# EN-C200_RA0_MCU.net
KiCad netlist of a schematic drawn in Altium Designer
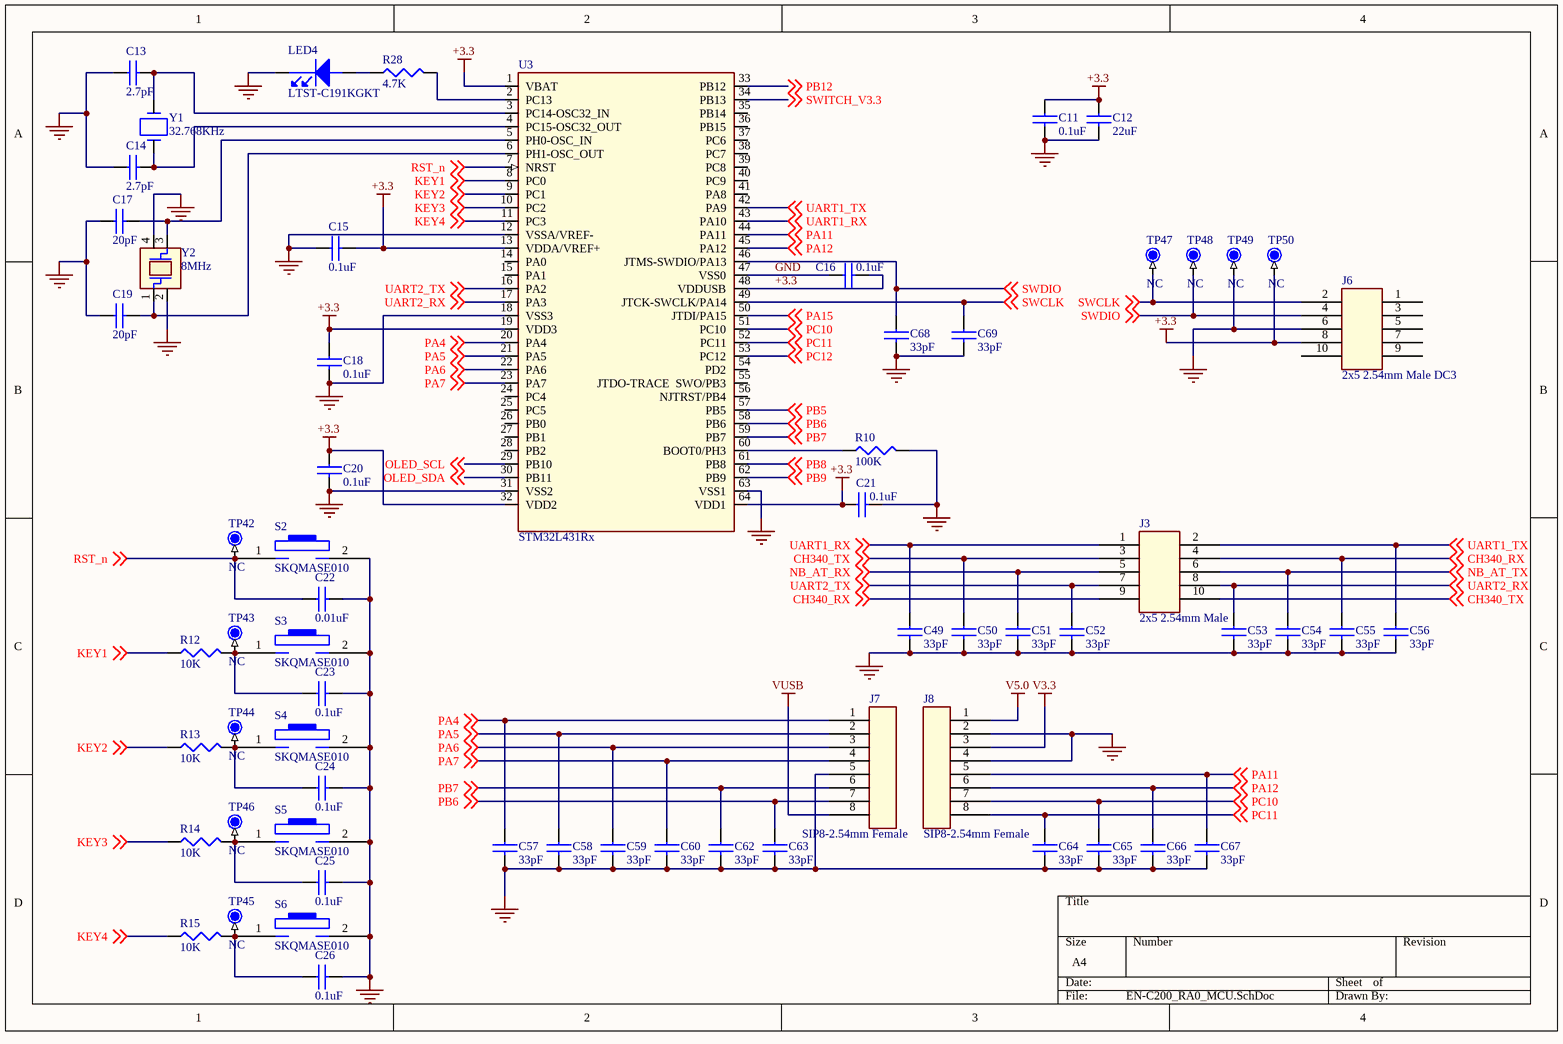
[diagram p0: EN-C200_RA0_MCU.SchDoc]

(export (version "E")
  (design (tool "Eeschema 10.0.6"))
  (components
    (comp (ref "C11") (value "0.1uF") (footprint "SC0603") (libsource (lib "EN-C200_RA0") (part "CAP NP")))
    (comp (ref "C12") (value "22uF") (footprint "SC0805") (libsource (lib "EN-C200_RA0") (part "CAP NP")))
    (comp (ref "C13") (value "2.7pF") (footprint "SC0603") (libsource (lib "EN-C200_RA0") (part "CAP NP")))
    (comp (ref "C14") (value "2.7pF") (footprint "SC0603") (libsource (lib "EN-C200_RA0") (part "CAP NP")))
    (comp (ref "C15") (value "0.1uF") (footprint "SC0603") (libsource (lib "EN-C200_RA0") (part "CAP NP")))
    (comp (ref "C16") (value "0.1uF") (footprint "SC0603") (libsource (lib "EN-C200_RA0") (part "CAP NP")))
    (comp (ref "C17") (value "20pF") (footprint "SC0603") (libsource (lib "EN-C200_RA0") (part "CAP NP")))
    (comp (ref "C18") (value "0.1uF") (footprint "SC0603") (libsource (lib "EN-C200_RA0") (part "CAP NP")))
    (comp (ref "C19") (value "20pF") (footprint "SC0603") (libsource (lib "EN-C200_RA0") (part "CAP NP")))
    (comp (ref "C20") (value "0.1uF") (footprint "SC0603") (libsource (lib "EN-C200_RA0") (part "CAP NP")))
    (comp (ref "C21") (value "0.1uF") (footprint "SC0603") (libsource (lib "EN-C200_RA0") (part "CAP NP")))
    (comp (ref "C22") (value "0.01uF") (footprint "SC0603") (libsource (lib "EN-C200_RA0") (part "CAP NP")))
    (comp (ref "C23") (value "0.1uF") (footprint "SC0603") (libsource (lib "EN-C200_RA0") (part "CAP NP")))
    (comp (ref "C24") (value "0.1uF") (footprint "SC0603") (libsource (lib "EN-C200_RA0") (part "CAP NP")))
    (comp (ref "C25") (value "0.1uF") (footprint "SC0603") (libsource (lib "EN-C200_RA0") (part "CAP NP")))
    (comp (ref "C26") (value "0.1uF") (footprint "SC0603") (libsource (lib "EN-C200_RA0") (part "CAP NP")))
    (comp (ref "C49") (value "33pF") (footprint "SC0603") (libsource (lib "EN-C200_RA0") (part "CAP NP")))
    (comp (ref "C50") (value "33pF") (footprint "SC0603") (libsource (lib "EN-C200_RA0") (part "CAP NP")))
    (comp (ref "C51") (value "33pF") (footprint "SC0603") (libsource (lib "EN-C200_RA0") (part "CAP NP")))
    (comp (ref "C52") (value "33pF") (footprint "SC0603") (libsource (lib "EN-C200_RA0") (part "CAP NP")))
    (comp (ref "C53") (value "33pF") (footprint "SC0603") (libsource (lib "EN-C200_RA0") (part "CAP NP")))
    (comp (ref "C54") (value "33pF") (footprint "SC0603") (libsource (lib "EN-C200_RA0") (part "CAP NP")))
    (comp (ref "C55") (value "33pF") (footprint "SC0603") (libsource (lib "EN-C200_RA0") (part "CAP NP")))
    (comp (ref "C56") (value "33pF") (footprint "SC0603") (libsource (lib "EN-C200_RA0") (part "CAP NP")))
    (comp (ref "C57") (value "33pF") (footprint "SC0603") (libsource (lib "EN-C200_RA0") (part "CAP NP")))
    (comp (ref "C58") (value "33pF") (footprint "SC0603") (libsource (lib "EN-C200_RA0") (part "CAP NP")))
    (comp (ref "C59") (value "33pF") (footprint "SC0603") (libsource (lib "EN-C200_RA0") (part "CAP NP")))
    (comp (ref "C60") (value "33pF") (footprint "SC0603") (libsource (lib "EN-C200_RA0") (part "CAP NP")))
    (comp (ref "C62") (value "33pF") (footprint "SC0603") (libsource (lib "EN-C200_RA0") (part "CAP NP")))
    (comp (ref "C63") (value "33pF") (footprint "SC0603") (libsource (lib "EN-C200_RA0") (part "CAP NP")))
    (comp (ref "C64") (value "33pF") (footprint "SC0603") (libsource (lib "EN-C200_RA0") (part "CAP NP")))
    (comp (ref "C65") (value "33pF") (footprint "SC0603") (libsource (lib "EN-C200_RA0") (part "CAP NP")))
    (comp (ref "C66") (value "33pF") (footprint "SC0603") (libsource (lib "EN-C200_RA0") (part "CAP NP")))
    (comp (ref "C67") (value "33pF") (footprint "SC0603") (libsource (lib "EN-C200_RA0") (part "CAP NP")))
    (comp (ref "C68") (value "33pF") (footprint "SC0603") (libsource (lib "EN-C200_RA0") (part "CAP NP")))
    (comp (ref "C69") (value "33pF") (footprint "SC0603") (libsource (lib "EN-C200_RA0") (part "CAP NP")))
    (comp (ref "J3")
      (value "2x5 2.54mm Male")
      (footprint "SIP-2X5P-100")
      (libsource (lib "") (part "CON10A_1"))
    )
    (comp (ref "J6")
      (value "2x5 2.54mm Male DC3")
      (footprint "SIP-2X5P-100-DS")
      (libsource (lib "EN-C200_RA0") (part "CON10A"))
    )
    (comp (ref "J7")
      (value "SIP8-2.54mm Female")
      (footprint "SIP-8P-100")
      (libsource (lib "EN-C200_RA0") (part "HEADER8"))
    )
    (comp (ref "J8")
      (value "SIP8-2.54mm Female")
      (footprint "SIP-8P-100")
      (libsource (lib "") (part "HEADER8_1"))
    )
    (comp (ref "LED4")
      (value "LTST-C191KGKT")
      (footprint "HSD0603-LED")
      (libsource (lib "EN-C200_RA0") (part "LED"))
    )
    (comp (ref "R10") (value "100K") (footprint "SR0603") (libsource (lib "EN-C200_RA0") (part "RESISTOR")))
    (comp (ref "R12") (value "10K") (footprint "SR0603") (libsource (lib "EN-C200_RA0") (part "RESISTOR")))
    (comp (ref "R13") (value "10K") (footprint "SR0603") (libsource (lib "EN-C200_RA0") (part "RESISTOR")))
    (comp (ref "R14") (value "10K") (footprint "SR0603") (libsource (lib "EN-C200_RA0") (part "RESISTOR")))
    (comp (ref "R15") (value "10K") (footprint "SR0603") (libsource (lib "EN-C200_RA0") (part "RESISTOR")))
    (comp (ref "R28") (value "4.7K") (footprint "SR0603") (libsource (lib "EN-C200_RA0") (part "RESISTOR")))
    (comp (ref "S2")
      (value "SKQMASE010")
      (footprint "SW2-240X140")
      (libsource (lib "EN-C200_RA0") (part "PUSH-KEY"))
    )
    (comp (ref "S3")
      (value "SKQMASE010")
      (footprint "SW2-240X140")
      (libsource (lib "EN-C200_RA0") (part "PUSH-KEY"))
    )
    (comp (ref "S4")
      (value "SKQMASE010")
      (footprint "SW2-240X140")
      (libsource (lib "EN-C200_RA0") (part "PUSH-KEY"))
    )
    (comp (ref "S5")
      (value "SKQMASE010")
      (footprint "SW2-240X140")
      (libsource (lib "EN-C200_RA0") (part "PUSH-KEY"))
    )
    (comp (ref "S6")
      (value "SKQMASE010")
      (footprint "SW2-240X140")
      (libsource (lib "EN-C200_RA0") (part "PUSH-KEY"))
    )
    (comp (ref "TP42") (value "NC") (footprint "TP32-SMD") (libsource (lib "EN-C200_RA0") (part "TP")))
    (comp (ref "TP43") (value "NC") (footprint "TP32-SMD") (libsource (lib "EN-C200_RA0") (part "TP")))
    (comp (ref "TP44") (value "NC") (footprint "TP32-SMD") (libsource (lib "EN-C200_RA0") (part "TP")))
    (comp (ref "TP45") (value "NC") (footprint "TP32-SMD") (libsource (lib "EN-C200_RA0") (part "TP")))
    (comp (ref "TP46") (value "NC") (footprint "TP32-SMD") (libsource (lib "EN-C200_RA0") (part "TP")))
    (comp (ref "TP47") (value "NC") (footprint "TP32-SMD") (libsource (lib "EN-C200_RA0") (part "TP")))
    (comp (ref "TP48") (value "NC") (footprint "TP32-SMD") (libsource (lib "EN-C200_RA0") (part "TP")))
    (comp (ref "TP49") (value "NC") (footprint "TP32-SMD") (libsource (lib "EN-C200_RA0") (part "TP")))
    (comp (ref "TP50") (value "NC") (footprint "TP32-SMD") (libsource (lib "EN-C200_RA0") (part "TP")))
    (comp (ref "U3")
      (value "STM32L431Rx")
      (footprint "QFP64D-050-1010L")
      (libsource (lib "EN-C200_RA0") (part "STM32L431Rx"))
    )
    (comp (ref "Y1")
      (value "32.768KHz")
      (footprint "FC-135_110")
      (libsource (lib "EN-C200_RA0") (part "CRYSTAL2P"))
    )
    (comp (ref "Y2")
      (value "8MHz")
      (footprint "HSX4-0503B")
      (libsource (lib "EN-C200_RA0") (part "CRYSTAL4P"))
    )
  )
  (nets
    (net (code "1") (name "+3.3") (class "Default")
      (node (ref "C11") (pin "1") (pinfunction "1_1") (pintype "passive"))
      (node (ref "C12") (pin "1") (pinfunction "1_1") (pintype "passive"))
      (node (ref "C15") (pin "2") (pinfunction "2_2") (pintype "passive"))
      (node (ref "C16") (pin "2") (pinfunction "2_2") (pintype "passive"))
      (node (ref "C18") (pin "1") (pinfunction "1_1") (pintype "passive"))
      (node (ref "C20") (pin "1") (pinfunction "1_1") (pintype "passive"))
      (node (ref "C21") (pin "1") (pinfunction "1_1") (pintype "passive"))
      (node (ref "J6") (pin "8") (pinfunction "8_8") (pintype "passive"))
      (node (ref "TP50") (pin "1") (pinfunction "1_1") (pintype "input"))
      (node (ref "U3") (pin "1") (pinfunction "VBAT_1") (pintype "power_in"))
      (node (ref "U3") (pin "13") (pinfunction "VDDA/VREF+_13") (pintype "power_in"))
      (node (ref "U3") (pin "19") (pinfunction "VDD3_19") (pintype "power_in"))
      (node (ref "U3") (pin "32") (pinfunction "VDD2_32") (pintype "power_in"))
      (node (ref "U3") (pin "48") (pinfunction "VDDUSB_48") (pintype "power_in"))
      (node (ref "U3") (pin "64") (pinfunction "VDD1_64") (pintype "power_in"))
    )
    (net (code "2") (name "CH340_RX") (class "Default")
      (node (ref "C55") (pin "1") (pinfunction "1_1") (pintype "passive"))
      (node (ref "J3") (pin "4") (pinfunction "4_4") (pintype "passive"))
      (node (ref "J3") (pin "9") (pinfunction "9_9") (pintype "passive"))
    )
    (net (code "3") (name "CH340_TX") (class "Default")
      (node (ref "C50") (pin "1") (pinfunction "1_1") (pintype "passive"))
      (node (ref "J3") (pin "10") (pinfunction "10_10") (pintype "passive"))
      (node (ref "J3") (pin "3") (pinfunction "3_3") (pintype "passive"))
    )
    (net (code "4") (name "GND") (class "Default")
      (node (ref "C11") (pin "2") (pinfunction "2_2") (pintype "passive"))
      (node (ref "C12") (pin "2") (pinfunction "2_2") (pintype "passive"))
      (node (ref "C13") (pin "1") (pinfunction "1_1") (pintype "passive"))
      (node (ref "C14") (pin "1") (pinfunction "1_1") (pintype "passive"))
      (node (ref "C15") (pin "1") (pinfunction "1_1") (pintype "passive"))
      (node (ref "C16") (pin "1") (pinfunction "1_1") (pintype "passive"))
      (node (ref "C17") (pin "1") (pinfunction "1_1") (pintype "passive"))
      (node (ref "C18") (pin "2") (pinfunction "2_2") (pintype "passive"))
      (node (ref "C19") (pin "1") (pinfunction "1_1") (pintype "passive"))
      (node (ref "C20") (pin "2") (pinfunction "2_2") (pintype "passive"))
      (node (ref "C21") (pin "2") (pinfunction "2_2") (pintype "passive"))
      (node (ref "C22") (pin "2") (pinfunction "2_2") (pintype "passive"))
      (node (ref "C23") (pin "2") (pinfunction "2_2") (pintype "passive"))
      (node (ref "C24") (pin "2") (pinfunction "2_2") (pintype "passive"))
      (node (ref "C25") (pin "2") (pinfunction "2_2") (pintype "passive"))
      (node (ref "C26") (pin "2") (pinfunction "2_2") (pintype "passive"))
      (node (ref "C49") (pin "2") (pinfunction "2_2") (pintype "passive"))
      (node (ref "C50") (pin "2") (pinfunction "2_2") (pintype "passive"))
      (node (ref "C51") (pin "2") (pinfunction "2_2") (pintype "passive"))
      (node (ref "C52") (pin "2") (pinfunction "2_2") (pintype "passive"))
      (node (ref "C53") (pin "2") (pinfunction "2_2") (pintype "passive"))
      (node (ref "C54") (pin "2") (pinfunction "2_2") (pintype "passive"))
      (node (ref "C55") (pin "2") (pinfunction "2_2") (pintype "passive"))
      (node (ref "C56") (pin "2") (pinfunction "2_2") (pintype "passive"))
      (node (ref "C57") (pin "2") (pinfunction "2_2") (pintype "passive"))
      (node (ref "C58") (pin "2") (pinfunction "2_2") (pintype "passive"))
      (node (ref "C59") (pin "2") (pinfunction "2_2") (pintype "passive"))
      (node (ref "C60") (pin "2") (pinfunction "2_2") (pintype "passive"))
      (node (ref "C62") (pin "2") (pinfunction "2_2") (pintype "passive"))
      (node (ref "C63") (pin "2") (pinfunction "2_2") (pintype "passive"))
      (node (ref "C64") (pin "2") (pinfunction "2_2") (pintype "passive"))
      (node (ref "C65") (pin "2") (pinfunction "2_2") (pintype "passive"))
      (node (ref "C66") (pin "2") (pinfunction "2_2") (pintype "passive"))
      (node (ref "C67") (pin "2") (pinfunction "2_2") (pintype "passive"))
      (node (ref "C68") (pin "2") (pinfunction "2_2") (pintype "passive"))
      (node (ref "C69") (pin "2") (pinfunction "2_2") (pintype "passive"))
      (node (ref "J6") (pin "6") (pinfunction "6_6") (pintype "passive"))
      (node (ref "J7") (pin "5") (pinfunction "5_5") (pintype "passive"))
      (node (ref "J8") (pin "2") (pinfunction "2_2") (pintype "passive"))
      (node (ref "J8") (pin "4") (pinfunction "4_4") (pintype "passive"))
      (node (ref "LED4") (pin "2") (pinfunction "2_2") (pintype "passive"))
      (node (ref "R10") (pin "2") (pinfunction "2_2") (pintype "passive"))
      (node (ref "S2") (pin "2") (pinfunction "B_2") (pintype "passive"))
      (node (ref "S3") (pin "2") (pinfunction "B_2") (pintype "passive"))
      (node (ref "S4") (pin "2") (pinfunction "B_2") (pintype "passive"))
      (node (ref "S5") (pin "2") (pinfunction "B_2") (pintype "passive"))
      (node (ref "S6") (pin "2") (pinfunction "B_2") (pintype "passive"))
      (node (ref "TP49") (pin "1") (pinfunction "1_1") (pintype "input"))
      (node (ref "U3") (pin "12") (pinfunction "VSSA/VREF-_12") (pintype "power_in"))
      (node (ref "U3") (pin "18") (pinfunction "VSS3_18") (pintype "power_in"))
      (node (ref "U3") (pin "31") (pinfunction "VSS2_31") (pintype "power_in"))
      (node (ref "U3") (pin "47") (pinfunction "VSS0_47") (pintype "power_in"))
      (node (ref "U3") (pin "63") (pinfunction "VSS1_63") (pintype "power_in"))
      (node (ref "Y2") (pin "2") (pinfunction "2_2") (pintype "passive"))
      (node (ref "Y2") (pin "4") (pinfunction "4_4") (pintype "passive"))
    )
    (net (code "5") (name "KEY1") (class "Default")
      (node (ref "R12") (pin "1") (pinfunction "1_1") (pintype "passive"))
      (node (ref "U3") (pin "8") (pinfunction "PC0_8") (pintype "bidirectional"))
    )
    (net (code "6") (name "KEY2") (class "Default")
      (node (ref "R13") (pin "1") (pinfunction "1_1") (pintype "passive"))
      (node (ref "U3") (pin "9") (pinfunction "PC1_9") (pintype "bidirectional"))
    )
    (net (code "7") (name "KEY3") (class "Default")
      (node (ref "R14") (pin "1") (pinfunction "1_1") (pintype "passive"))
      (node (ref "U3") (pin "10") (pinfunction "PC2_10") (pintype "bidirectional"))
    )
    (net (code "8") (name "KEY4") (class "Default")
      (node (ref "R15") (pin "1") (pinfunction "1_1") (pintype "passive"))
      (node (ref "U3") (pin "11") (pinfunction "PC3_11") (pintype "bidirectional"))
    )
    (net (code "9") (name "NB_AT_RX") (class "Default")
      (node (ref "C51") (pin "1") (pinfunction "1_1") (pintype "passive"))
      (node (ref "J3") (pin "5") (pinfunction "5_5") (pintype "passive"))
    )
    (net (code "10") (name "NB_AT_TX") (class "Default")
      (node (ref "C54") (pin "1") (pinfunction "1_1") (pintype "passive"))
      (node (ref "J3") (pin "6") (pinfunction "6_6") (pintype "passive"))
    )
    (net (code "11") (name "Net-(LED4-Pad1)") (class "Default")
      (node (ref "LED4") (pin "1") (pinfunction "1_1") (pintype "passive"))
      (node (ref "R28") (pin "1") (pinfunction "1_1") (pintype "passive"))
    )
    (net (code "12") (name "Net-(S3-A)") (class "Default")
      (node (ref "C23") (pin "1") (pinfunction "1_1") (pintype "passive"))
      (node (ref "R12") (pin "2") (pinfunction "2_2") (pintype "passive"))
      (node (ref "S3") (pin "1") (pinfunction "A_1") (pintype "passive"))
      (node (ref "TP43") (pin "1") (pinfunction "1_1") (pintype "input"))
    )
    (net (code "13") (name "Net-(S4-A)") (class "Default")
      (node (ref "C24") (pin "1") (pinfunction "1_1") (pintype "passive"))
      (node (ref "R13") (pin "2") (pinfunction "2_2") (pintype "passive"))
      (node (ref "S4") (pin "1") (pinfunction "A_1") (pintype "passive"))
      (node (ref "TP44") (pin "1") (pinfunction "1_1") (pintype "input"))
    )
    (net (code "14") (name "Net-(S5-A)") (class "Default")
      (node (ref "C25") (pin "1") (pinfunction "1_1") (pintype "passive"))
      (node (ref "R14") (pin "2") (pinfunction "2_2") (pintype "passive"))
      (node (ref "S5") (pin "1") (pinfunction "A_1") (pintype "passive"))
      (node (ref "TP46") (pin "1") (pinfunction "1_1") (pintype "input"))
    )
    (net (code "15") (name "Net-(S6-A)") (class "Default")
      (node (ref "C26") (pin "1") (pinfunction "1_1") (pintype "passive"))
      (node (ref "R15") (pin "2") (pinfunction "2_2") (pintype "passive"))
      (node (ref "S6") (pin "1") (pinfunction "A_1") (pintype "passive"))
      (node (ref "TP45") (pin "1") (pinfunction "1_1") (pintype "input"))
    )
    (net (code "16") (name "Net-(U3-BOOT0{slash}PH3)") (class "Default")
      (node (ref "R10") (pin "1") (pinfunction "1_1") (pintype "passive"))
      (node (ref "U3") (pin "60") (pinfunction "BOOT0/PH3_60") (pintype "bidirectional"))
    )
    (net (code "17") (name "Net-(U3-PC13)") (class "Default")
      (node (ref "R28") (pin "2") (pinfunction "2_2") (pintype "passive"))
      (node (ref "U3") (pin "2") (pinfunction "PC13_2") (pintype "bidirectional"))
    )
    (net (code "18") (name "Net-(U3-PC14-OSC32_IN)") (class "Default")
      (node (ref "C13") (pin "2") (pinfunction "2_2") (pintype "passive"))
      (node (ref "U3") (pin "3") (pinfunction "PC14-OSC32_IN_3") (pintype "bidirectional"))
      (node (ref "Y1") (pin "2") (pinfunction "2_2") (pintype "passive"))
    )
    (net (code "19") (name "Net-(U3-PC15-OSC32_OUT)") (class "Default")
      (node (ref "C14") (pin "2") (pinfunction "2_2") (pintype "passive"))
      (node (ref "U3") (pin "4") (pinfunction "PC15-OSC32_OUT_4") (pintype "bidirectional"))
      (node (ref "Y1") (pin "1") (pinfunction "1_1") (pintype "passive"))
    )
    (net (code "20") (name "Net-(U3-PH0-OSC_IN)") (class "Default")
      (node (ref "C17") (pin "2") (pinfunction "2_2") (pintype "passive"))
      (node (ref "U3") (pin "5") (pinfunction "PH0-OSC_IN_5") (pintype "bidirectional"))
      (node (ref "Y2") (pin "3") (pinfunction "COUT_3") (pintype "passive"))
    )
    (net (code "21") (name "Net-(U3-PH1-OSC_OUT)") (class "Default")
      (node (ref "C19") (pin "2") (pinfunction "2_2") (pintype "passive"))
      (node (ref "U3") (pin "6") (pinfunction "PH1-OSC_OUT_6") (pintype "bidirectional"))
      (node (ref "Y2") (pin "1") (pinfunction "CIN_1") (pintype "passive"))
    )
    (net (code "22") (name "OLED_SCL") (class "Default")
      (node (ref "U3") (pin "29") (pinfunction "PB10_29") (pintype "bidirectional"))
    )
    (net (code "23") (name "OLED_SDA") (class "Default")
      (node (ref "U3") (pin "30") (pinfunction "PB11_30") (pintype "bidirectional"))
    )
    (net (code "24") (name "PA4") (class "Default")
      (node (ref "C57") (pin "1") (pinfunction "1_1") (pintype "passive"))
      (node (ref "J7") (pin "1") (pinfunction "1_1") (pintype "passive"))
      (node (ref "U3") (pin "20") (pinfunction "PA4_20") (pintype "bidirectional"))
    )
    (net (code "25") (name "PA5") (class "Default")
      (node (ref "C58") (pin "1") (pinfunction "1_1") (pintype "passive"))
      (node (ref "J7") (pin "2") (pinfunction "2_2") (pintype "passive"))
      (node (ref "U3") (pin "21") (pinfunction "PA5_21") (pintype "bidirectional"))
    )
    (net (code "26") (name "PA6") (class "Default")
      (node (ref "C59") (pin "1") (pinfunction "1_1") (pintype "passive"))
      (node (ref "J7") (pin "3") (pinfunction "3_3") (pintype "passive"))
      (node (ref "U3") (pin "22") (pinfunction "PA6_22") (pintype "bidirectional"))
    )
    (net (code "27") (name "PA7") (class "Default")
      (node (ref "C60") (pin "1") (pinfunction "1_1") (pintype "passive"))
      (node (ref "J7") (pin "4") (pinfunction "4_4") (pintype "passive"))
      (node (ref "U3") (pin "23") (pinfunction "PA7_23") (pintype "bidirectional"))
    )
    (net (code "28") (name "PA11") (class "Default")
      (node (ref "C67") (pin "1") (pinfunction "1_1") (pintype "passive"))
      (node (ref "J8") (pin "5") (pinfunction "5_5") (pintype "passive"))
      (node (ref "U3") (pin "44") (pinfunction "PA11_44") (pintype "bidirectional"))
    )
    (net (code "29") (name "PA12") (class "Default")
      (node (ref "C66") (pin "1") (pinfunction "1_1") (pintype "passive"))
      (node (ref "J8") (pin "6") (pinfunction "6_6") (pintype "passive"))
      (node (ref "U3") (pin "45") (pinfunction "PA12_45") (pintype "bidirectional"))
    )
    (net (code "30") (name "PA15") (class "Default")
      (node (ref "U3") (pin "50") (pinfunction "JTDI/PA15_50") (pintype "bidirectional"))
    )
    (net (code "31") (name "PB5") (class "Default")
      (node (ref "U3") (pin "57") (pinfunction "PB5_57") (pintype "bidirectional"))
    )
    (net (code "32") (name "PB6") (class "Default")
      (node (ref "C63") (pin "1") (pinfunction "1_1") (pintype "passive"))
      (node (ref "J7") (pin "7") (pinfunction "7_7") (pintype "passive"))
      (node (ref "U3") (pin "58") (pinfunction "PB6_58") (pintype "bidirectional"))
    )
    (net (code "33") (name "PB7") (class "Default")
      (node (ref "C62") (pin "1") (pinfunction "1_1") (pintype "passive"))
      (node (ref "J7") (pin "6") (pinfunction "6_6") (pintype "passive"))
      (node (ref "U3") (pin "59") (pinfunction "PB7_59") (pintype "bidirectional"))
    )
    (net (code "34") (name "PB8") (class "Default")
      (node (ref "U3") (pin "61") (pinfunction "PB8_61") (pintype "bidirectional"))
    )
    (net (code "35") (name "PB9") (class "Default")
      (node (ref "U3") (pin "62") (pinfunction "PB9_62") (pintype "bidirectional"))
    )
    (net (code "36") (name "PB12") (class "Default")
      (node (ref "U3") (pin "33") (pinfunction "PB12_33") (pintype "bidirectional"))
    )
    (net (code "37") (name "PC10") (class "Default")
      (node (ref "C65") (pin "1") (pinfunction "1_1") (pintype "passive"))
      (node (ref "J8") (pin "7") (pinfunction "7_7") (pintype "passive"))
      (node (ref "U3") (pin "51") (pinfunction "PC10_51") (pintype "bidirectional"))
    )
    (net (code "38") (name "PC11") (class "Default")
      (node (ref "C64") (pin "1") (pinfunction "1_1") (pintype "passive"))
      (node (ref "J8") (pin "8") (pinfunction "8_8") (pintype "passive"))
      (node (ref "U3") (pin "52") (pinfunction "PC11_52") (pintype "bidirectional"))
    )
    (net (code "39") (name "PC12") (class "Default")
      (node (ref "U3") (pin "53") (pinfunction "PC12_53") (pintype "bidirectional"))
    )
    (net (code "40") (name "RST_n") (class "Default")
      (node (ref "C22") (pin "1") (pinfunction "1_1") (pintype "passive"))
      (node (ref "S2") (pin "1") (pinfunction "A_1") (pintype "passive"))
      (node (ref "TP42") (pin "1") (pinfunction "1_1") (pintype "input"))
      (node (ref "U3") (pin "7") (pinfunction "NRST_7") (pintype "input"))
    )
    (net (code "41") (name "SWCLK") (class "Default")
      (node (ref "C69") (pin "1") (pinfunction "1_1") (pintype "passive"))
      (node (ref "J6") (pin "2") (pinfunction "2_2") (pintype "passive"))
      (node (ref "TP47") (pin "1") (pinfunction "1_1") (pintype "input"))
      (node (ref "U3") (pin "49") (pinfunction "JTCK-SWCLK/PA14_49") (pintype "bidirectional"))
    )
    (net (code "42") (name "SWDIO") (class "Default")
      (node (ref "C68") (pin "1") (pinfunction "1_1") (pintype "passive"))
      (node (ref "J6") (pin "4") (pinfunction "4_4") (pintype "passive"))
      (node (ref "TP48") (pin "1") (pinfunction "1_1") (pintype "input"))
      (node (ref "U3") (pin "46") (pinfunction "JTMS-SWDIO/PA13_46") (pintype "bidirectional"))
    )
    (net (code "43") (name "SWITCH_V3.3") (class "Default")
      (node (ref "U3") (pin "34") (pinfunction "PB13_34") (pintype "bidirectional"))
    )
    (net (code "44") (name "UART1_RX") (class "Default")
      (node (ref "C49") (pin "1") (pinfunction "1_1") (pintype "passive"))
      (node (ref "J3") (pin "1") (pinfunction "1_1") (pintype "passive"))
      (node (ref "U3") (pin "43") (pinfunction "PA10_43") (pintype "bidirectional"))
    )
    (net (code "45") (name "UART1_TX") (class "Default")
      (node (ref "C56") (pin "1") (pinfunction "1_1") (pintype "passive"))
      (node (ref "J3") (pin "2") (pinfunction "2_2") (pintype "passive"))
      (node (ref "U3") (pin "42") (pinfunction "PA9_42") (pintype "bidirectional"))
    )
    (net (code "46") (name "UART2_RX") (class "Default")
      (node (ref "C53") (pin "1") (pinfunction "1_1") (pintype "passive"))
      (node (ref "J3") (pin "8") (pinfunction "8_8") (pintype "passive"))
      (node (ref "U3") (pin "17") (pinfunction "PA3_17") (pintype "bidirectional"))
    )
    (net (code "47") (name "UART2_TX") (class "Default")
      (node (ref "C52") (pin "1") (pinfunction "1_1") (pintype "passive"))
      (node (ref "J3") (pin "7") (pinfunction "7_7") (pintype "passive"))
      (node (ref "U3") (pin "16") (pinfunction "PA2_16") (pintype "bidirectional"))
    )
    (net (code "48") (name "V3.3") (class "Default")
      (node (ref "J8") (pin "3") (pinfunction "3_3") (pintype "passive"))
    )
    (net (code "49") (name "V5.0") (class "Default")
      (node (ref "J8") (pin "1") (pinfunction "1_1") (pintype "passive"))
    )
    (net (code "50") (name "VUSB") (class "Default")
      (node (ref "J7") (pin "8") (pinfunction "8_8") (pintype "passive"))
    )
    (net (code "51") (name "unconnected-(J6-Pad1)") (class "Default")
      (node (ref "J6") (pin "1") (pinfunction "1_1") (pintype "passive"))
    )
    (net (code "52") (name "unconnected-(J6-Pad3)") (class "Default")
      (node (ref "J6") (pin "3") (pinfunction "3_3") (pintype "passive"))
    )
    (net (code "53") (name "unconnected-(J6-Pad5)") (class "Default")
      (node (ref "J6") (pin "5") (pinfunction "5_5") (pintype "passive"))
    )
    (net (code "54") (name "unconnected-(J6-Pad7)") (class "Default")
      (node (ref "J6") (pin "7") (pinfunction "7_7") (pintype "passive"))
    )
    (net (code "55") (name "unconnected-(J6-Pad9)") (class "Default")
      (node (ref "J6") (pin "9") (pinfunction "9_9") (pintype "passive"))
    )
    (net (code "56") (name "unconnected-(J6-Pad10)") (class "Default")
      (node (ref "J6") (pin "10") (pinfunction "10_10") (pintype "passive"))
    )
    (net (code "57") (name "unconnected-(U3-JTDO-TRACE__SWO{slash}PB3-Pad55)") (class "Default")
      (node (ref "U3") (pin "55") (pinfunction "JTDO-TRACE__SWO/PB3_55") (pintype "bidirectional"))
    )
    (net (code "58") (name "unconnected-(U3-NJTRST{slash}PB4-Pad56)") (class "Default")
      (node (ref "U3") (pin "56") (pinfunction "NJTRST/PB4_56") (pintype "bidirectional"))
    )
    (net (code "59") (name "unconnected-(U3-PA0-Pad14)") (class "Default")
      (node (ref "U3") (pin "14") (pinfunction "PA0_14") (pintype "bidirectional"))
    )
    (net (code "60") (name "unconnected-(U3-PA1-Pad15)") (class "Default")
      (node (ref "U3") (pin "15") (pinfunction "PA1_15") (pintype "bidirectional"))
    )
    (net (code "61") (name "unconnected-(U3-PA8-Pad41)") (class "Default")
      (node (ref "U3") (pin "41") (pinfunction "PA8_41") (pintype "bidirectional"))
    )
    (net (code "62") (name "unconnected-(U3-PB0-Pad26)") (class "Default")
      (node (ref "U3") (pin "26") (pinfunction "PB0_26") (pintype "bidirectional"))
    )
    (net (code "63") (name "unconnected-(U3-PB1-Pad27)") (class "Default")
      (node (ref "U3") (pin "27") (pinfunction "PB1_27") (pintype "bidirectional"))
    )
    (net (code "64") (name "unconnected-(U3-PB2-Pad28)") (class "Default")
      (node (ref "U3") (pin "28") (pinfunction "PB2_28") (pintype "bidirectional"))
    )
    (net (code "65") (name "unconnected-(U3-PB14-Pad35)") (class "Default")
      (node (ref "U3") (pin "35") (pinfunction "PB14_35") (pintype "bidirectional"))
    )
    (net (code "66") (name "unconnected-(U3-PB15-Pad36)") (class "Default")
      (node (ref "U3") (pin "36") (pinfunction "PB15_36") (pintype "bidirectional"))
    )
    (net (code "67") (name "unconnected-(U3-PC4-Pad24)") (class "Default")
      (node (ref "U3") (pin "24") (pinfunction "PC4_24") (pintype "bidirectional"))
    )
    (net (code "68") (name "unconnected-(U3-PC5-Pad25)") (class "Default")
      (node (ref "U3") (pin "25") (pinfunction "PC5_25") (pintype "bidirectional"))
    )
    (net (code "69") (name "unconnected-(U3-PC6-Pad37)") (class "Default")
      (node (ref "U3") (pin "37") (pinfunction "PC6_37") (pintype "bidirectional"))
    )
    (net (code "70") (name "unconnected-(U3-PC7-Pad38)") (class "Default")
      (node (ref "U3") (pin "38") (pinfunction "PC7_38") (pintype "bidirectional"))
    )
    (net (code "71") (name "unconnected-(U3-PC8-Pad39)") (class "Default")
      (node (ref "U3") (pin "39") (pinfunction "PC8_39") (pintype "bidirectional"))
    )
    (net (code "72") (name "unconnected-(U3-PC9-Pad40)") (class "Default")
      (node (ref "U3") (pin "40") (pinfunction "PC9_40") (pintype "bidirectional"))
    )
    (net (code "73") (name "unconnected-(U3-PD2-Pad54)") (class "Default")
      (node (ref "U3") (pin "54") (pinfunction "PD2_54") (pintype "bidirectional"))
    )
  )
)
